# Sheet3.net
KiCad netlist of a schematic drawn in Altium Designer
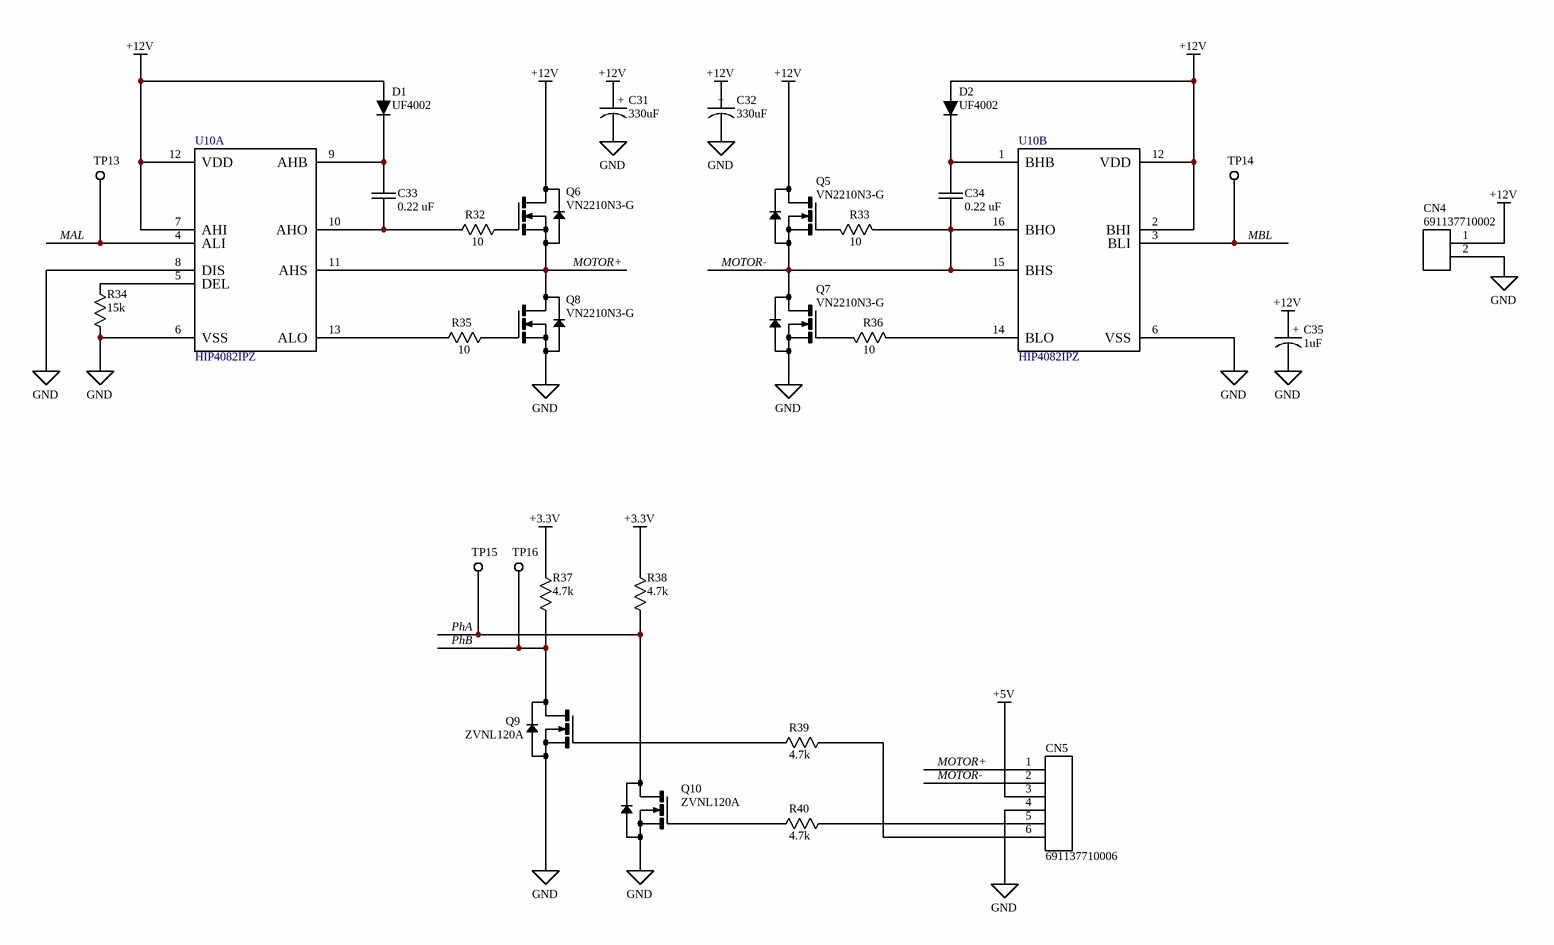
[diagram p0: Sheet3.SchDoc]

(export (version "E")
  (design (tool "Eeschema 10.0.6"))
  (components
    (comp (ref "C31")
      (value "330uF")
      (footprint "ECA-1EM331")
      (description "330 uF, 25 V Aluminum Electrolytic Capacitor")
      (fields
        (field (name "MANUFACTURER") "Panasonic Corporation of North America")
        (field (name "PARTNUMBER") "ECA-1EM331")
      )
      (libsource (lib "Schlib1") (part "ECA-1EM331"))
    )
    (comp (ref "C32")
      (value "330uF")
      (footprint "ECA-1EM331")
      (description "330 uF, 25 V Aluminum Electrolytic Capacitor")
      (fields
        (field (name "MANUFACTURER") "Panasonic Corporation of North America")
        (field (name "PARTNUMBER") "ECA-1EM331")
      )
      (libsource (lib "") (part "ECA-1EM331_1"))
    )
    (comp (ref "C33")
      (value "0.22 uF")
      (footprint "C330C224K1R5TA7301")
      (description "0.22 uF, 100 V Ceramic Capacitor")
      (fields (field (name "MANUFACTURER") "Kemet") (field (name "PARTNUMBER") "C330C224K1R5TA7301"))
      (libsource (lib "Schlib1") (part "C330C224K1R5TA7301"))
    )
    (comp (ref "C34")
      (value "0.22 uF")
      (footprint "C330C224K1R5TA7301")
      (description "0.22 uF, 100 V Ceramic Capacitor")
      (fields (field (name "MANUFACTURER") "Kemet") (field (name "PARTNUMBER") "C330C224K1R5TA7301"))
      (libsource (lib "Schlib1") (part "C330C224K1R5TA7301"))
    )
    (comp (ref "C35")
      (value "1uF")
      (footprint "SR215E105MAR")
      (description "1 uF, 50 V Ceramic Capacitor")
      (fields (field (name "MANUFACTURER") "AVX Corporation") (field (name "PARTNUMBER") "SR215E105MAR"))
      (libsource (lib "Schlib1") (part "SR215E105MAR"))
    )
    (comp (ref "CN4")
      (value "691137710002")
      (footprint "691137710002")
      (description "TERM BLK 2POS SIDE ENTRY 5MM PCB")
      (fields (field (name "MANUFACTURER") "Wurth Elektronk"))
      (libsource (lib "Schlib1") (part "691137710002"))
    )
    (comp (ref "CN5")
      (value "691137710006")
      (footprint "691137710006")
      (description "TERM BLK 6POS SIDE ENTRY 5MM PCB")
      (fields (field (name "MANUFACTURER") "Wurth Elektronik"))
      (libsource (lib "Schlib1") (part "691137710006"))
    )
    (comp (ref "D1")
      (value "UF4002")
      (footprint "UF4002")
      (description "Fast Rectifier")
      (fields (field (name "MANUFACTURER") "ON Semiconductor"))
      (libsource (lib "Schlib1") (part "UF4002"))
    )
    (comp (ref "D2")
      (value "UF4002")
      (footprint "UF4002")
      (description "Fast Rectifier")
      (fields (field (name "MANUFACTURER") "ON Semiconductor"))
      (libsource (lib "Schlib1") (part "UF4002"))
    )
    (comp (ref "Q5")
      (value "VN2210N3-G")
      (footprint "VN2210N3-G")
      (description "N-Channel Enhancement-Mode Vertical DMOS FETs")
      (fields (field (name "MANUFACTURER") "Supertex Inc."))
      (libsource (lib "") (part "VN2210N3-G_1"))
    )
    (comp (ref "Q6")
      (value "VN2210N3-G")
      (footprint "VN2210N3-G")
      (description "N-Channel Enhancement-Mode Vertical DMOS FETs")
      (fields (field (name "MANUFACTURER") "Supertex Inc."))
      (libsource (lib "Schlib1") (part "VN2210N3-G"))
    )
    (comp (ref "Q7")
      (value "VN2210N3-G")
      (footprint "VN2210N3-G")
      (description "N-Channel Enhancement-Mode Vertical DMOS FETs")
      (fields (field (name "MANUFACTURER") "Supertex Inc."))
      (libsource (lib "") (part "VN2210N3-G_1"))
    )
    (comp (ref "Q8")
      (value "VN2210N3-G")
      (footprint "VN2210N3-G")
      (description "N-Channel Enhancement-Mode Vertical DMOS FETs")
      (fields (field (name "MANUFACTURER") "Supertex Inc."))
      (libsource (lib "Schlib1") (part "VN2210N3-G"))
    )
    (comp (ref "Q9")
      (value "ZVNL120A")
      (footprint "ZVNL120A")
      (description "25V, 31 A, N-Channel Power MOSFET")
      (fields (field (name "MANUFACTURER") "Diodes Inc"))
      (libsource (lib "Schlib1") (part "ZVNL120A"))
    )
    (comp (ref "Q10")
      (value "ZVNL120A")
      (footprint "ZVNL120A")
      (description "25V, 31 A, N-Channel Power MOSFET")
      (fields (field (name "MANUFACTURER") "Diodes Inc"))
      (libsource (lib "Schlib1") (part "ZVNL120A"))
    )
    (comp (ref "R32")
      (value "10")
      (footprint "1/2WattResistor")
      (description "10 Ohmn, ±5%, 0.5W Thru-Hole Resistor")
      (fields (field (name "MANUFACTURER") "Generic") (field (name "PARTNUMBER") "RES10-500mW-THRU-HOLE"))
      (libsource (lib "Schlib1") (part "RES10-500mW-THRU-HOLE"))
    )
    (comp (ref "R33")
      (value "10")
      (footprint "1/2WattResistor")
      (description "10 Ohmn, ±5%, 0.5W Thru-Hole Resistor")
      (fields (field (name "MANUFACTURER") "Generic") (field (name "PARTNUMBER") "RES10-500mW-THRU-HOLE"))
      (libsource (lib "Schlib1") (part "RES10-500mW-THRU-HOLE"))
    )
    (comp (ref "R34")
      (value "15k")
      (footprint "1/2WattResistor")
      (description "15 kOhm, ±5%, 0.5W Thru-Hole Resistor")
      (fields (field (name "MANUFACTURER") "Generic") (field (name "PARTNUMBER") "RES15k-500mW-THRU-HOLE"))
      (libsource (lib "Schlib1") (part "RES15k-500mW-THRU-HOLE"))
    )
    (comp (ref "R35")
      (value "10")
      (footprint "1/2WattResistor")
      (description "10 Ohmn, ±5%, 0.5W Thru-Hole Resistor")
      (fields (field (name "MANUFACTURER") "Generic") (field (name "PARTNUMBER") "RES10-500mW-THRU-HOLE"))
      (libsource (lib "Schlib1") (part "RES10-500mW-THRU-HOLE"))
    )
    (comp (ref "R36")
      (value "10")
      (footprint "1/2WattResistor")
      (description "10 Ohmn, ±5%, 0.5W Thru-Hole Resistor")
      (fields (field (name "MANUFACTURER") "Generic") (field (name "PARTNUMBER") "RES10-500mW-THRU-HOLE"))
      (libsource (lib "Schlib1") (part "RES10-500mW-THRU-HOLE"))
    )
    (comp (ref "R37")
      (value "4.7k")
      (footprint "1/2WattResistor")
      (description "4.7 kOhm, ±5%, 0.5W Thru-Hole Resistor")
      (fields (field (name "MANUFACTURER") "Generic") (field (name "PARTNUMBER") "RES4k7-500mW-THRU-HOLE"))
      (libsource (lib "Schlib1") (part "RES4k7-500mW-THRU-HOLE"))
    )
    (comp (ref "R38")
      (value "4.7k")
      (footprint "1/2WattResistor")
      (description "4.7 kOhm, ±5%, 0.5W Thru-Hole Resistor")
      (fields (field (name "MANUFACTURER") "Generic") (field (name "PARTNUMBER") "RES4k7-500mW-THRU-HOLE"))
      (libsource (lib "Schlib1") (part "RES4k7-500mW-THRU-HOLE"))
    )
    (comp (ref "R39")
      (value "4.7k")
      (footprint "1/2WattResistor")
      (description "4.7 kOhm, ±5%, 0.5W Thru-Hole Resistor")
      (fields (field (name "MANUFACTURER") "Generic") (field (name "PARTNUMBER") "RES4k7-500mW-THRU-HOLE"))
      (libsource (lib "Schlib1") (part "RES4k7-500mW-THRU-HOLE"))
    )
    (comp (ref "R40")
      (value "4.7k")
      (footprint "1/2WattResistor")
      (description "4.7 kOhm, ±5%, 0.5W Thru-Hole Resistor")
      (fields (field (name "MANUFACTURER") "Generic") (field (name "PARTNUMBER") "RES4k7-500mW-THRU-HOLE"))
      (libsource (lib "Schlib1") (part "RES4k7-500mW-THRU-HOLE"))
    )
    (comp (ref "TP13")
      (value "TESTPOINT-2MM")
      (footprint "TESTPOINT-2MM")
      (description "Test Point 2MM diameter")
      (libsource (lib "Schlib1") (part "TESTPOINT-2MM"))
    )
    (comp (ref "TP14")
      (value "TESTPOINT-2MM")
      (footprint "TESTPOINT-2MM")
      (description "Test Point 2MM diameter")
      (libsource (lib "Schlib1") (part "TESTPOINT-2MM"))
    )
    (comp (ref "TP15")
      (value "TESTPOINT-2MM")
      (footprint "TESTPOINT-2MM")
      (description "Test Point 2MM diameter")
      (libsource (lib "Schlib1") (part "TESTPOINT-2MM"))
    )
    (comp (ref "TP16")
      (value "TESTPOINT-2MM")
      (footprint "TESTPOINT-2MM")
      (description "Test Point 2MM diameter")
      (libsource (lib "Schlib1") (part "TESTPOINT-2MM"))
    )
    (comp (ref "U10")
      (value "HIP4082IPZ")
      (footprint "HIP4082IPZ")
      (description "80V, 1.25A Peak Current H-Bridge FET Driver")
      (fields (field (name "MANUFACTURER") "Renesas"))
      (libsource (lib "Schlib1") (part "HIP4082IPZ"))
    )
  )
  (nets
    (net (code "1") (name "+3.3V") (class "Default")
      (node (ref "R37") (pin "2") (pinfunction "2_2") (pintype "passive"))
      (node (ref "R38") (pin "2") (pinfunction "2_2") (pintype "passive"))
    )
    (net (code "2") (name "+5V") (class "Default")
      (node (ref "CN5") (pin "3") (pinfunction "3_3") (pintype "passive"))
    )
    (net (code "3") (name "+12V") (class "Default")
      (node (ref "C31") (pin "1") (pinfunction "1_1") (pintype "passive"))
      (node (ref "C32") (pin "1") (pinfunction "1_1") (pintype "passive"))
      (node (ref "C35") (pin "1") (pinfunction "1_1") (pintype "passive"))
      (node (ref "CN4") (pin "1") (pinfunction "1_1") (pintype "passive"))
      (node (ref "D1") (pin "A") (pinfunction "A_A") (pintype "passive"))
      (node (ref "D2") (pin "A") (pinfunction "A_A") (pintype "passive"))
      (node (ref "Q5") (pin "3") (pinfunction "3_3") (pintype "passive"))
      (node (ref "Q6") (pin "3") (pinfunction "3_3") (pintype "passive"))
      (node (ref "U10") (pin "12") (pinfunction "VDD_12") (pintype "passive"))
      (node (ref "U10") (pin "2") (pinfunction "BHI_2") (pintype "passive"))
      (node (ref "U10") (pin "7") (pinfunction "AHI_7") (pintype "passive"))
    )
    (net (code "4") (name "/MAL") (class "Default")
      (node (ref "TP13") (pin "1") (pintype "passive"))
      (node (ref "U10") (pin "4") (pinfunction "ALI_4") (pintype "passive"))
    )
    (net (code "5") (name "/MBL") (class "Default")
      (node (ref "TP14") (pin "1") (pintype "passive"))
      (node (ref "U10") (pin "3") (pinfunction "BLI_3") (pintype "passive"))
    )
    (net (code "6") (name "/MOTOR+") (class "Default")
      (node (ref "CN5") (pin "1") (pinfunction "1_1") (pintype "passive"))
      (node (ref "Q6") (pin "1") (pinfunction "1_1") (pintype "passive"))
      (node (ref "Q8") (pin "3") (pinfunction "3_3") (pintype "passive"))
      (node (ref "U10") (pin "11") (pinfunction "AHS_11") (pintype "passive"))
    )
    (net (code "7") (name "/MOTOR-") (class "Default")
      (node (ref "C34") (pin "2") (pinfunction "2_2") (pintype "passive"))
      (node (ref "CN5") (pin "2") (pinfunction "2_2") (pintype "passive"))
      (node (ref "Q5") (pin "1") (pinfunction "1_1") (pintype "passive"))
      (node (ref "Q7") (pin "3") (pinfunction "3_3") (pintype "passive"))
      (node (ref "R33") (pin "1") (pinfunction "1_1") (pintype "passive"))
      (node (ref "U10") (pin "15") (pinfunction "BHS_15") (pintype "passive"))
      (node (ref "U10") (pin "16") (pinfunction "BHO_16") (pintype "passive"))
    )
    (net (code "8") (name "/PhA") (class "Default")
      (node (ref "Q10") (pin "3") (pinfunction "3_3") (pintype "passive"))
      (node (ref "R38") (pin "1") (pinfunction "1_1") (pintype "passive"))
      (node (ref "TP15") (pin "1") (pintype "passive"))
    )
    (net (code "9") (name "/PhB") (class "Default")
      (node (ref "Q9") (pin "3") (pinfunction "3_3") (pintype "passive"))
      (node (ref "R37") (pin "1") (pinfunction "1_1") (pintype "passive"))
      (node (ref "TP16") (pin "1") (pintype "passive"))
    )
    (net (code "10") (name "GND") (class "Default")
      (node (ref "C31") (pin "2") (pinfunction "2_2") (pintype "passive"))
      (node (ref "C32") (pin "2") (pinfunction "2_2") (pintype "passive"))
      (node (ref "C35") (pin "2") (pinfunction "2_2") (pintype "passive"))
      (node (ref "CN4") (pin "2") (pinfunction "2_2") (pintype "passive"))
      (node (ref "CN5") (pin "4") (pinfunction "4_4") (pintype "passive"))
      (node (ref "Q10") (pin "1") (pinfunction "1_1") (pintype "passive"))
      (node (ref "Q7") (pin "1") (pinfunction "1_1") (pintype "passive"))
      (node (ref "Q8") (pin "1") (pinfunction "1_1") (pintype "passive"))
      (node (ref "Q9") (pin "1") (pinfunction "1_1") (pintype "passive"))
      (node (ref "R34") (pin "1") (pinfunction "1_1") (pintype "passive"))
      (node (ref "U10") (pin "6") (pinfunction "VSS_6") (pintype "passive"))
      (node (ref "U10") (pin "8") (pinfunction "DIS_8") (pintype "passive"))
    )
    (net (code "11") (name "Net-(CN5-Pad5)") (class "Default")
      (node (ref "CN5") (pin "5") (pinfunction "5_5") (pintype "passive"))
      (node (ref "R40") (pin "2") (pinfunction "2_2") (pintype "passive"))
    )
    (net (code "12") (name "Net-(CN5-Pad6)") (class "Default")
      (node (ref "CN5") (pin "6") (pinfunction "6_6") (pintype "passive"))
      (node (ref "R39") (pin "2") (pinfunction "2_2") (pintype "passive"))
    )
    (net (code "13") (name "Net-(Q5-Pad2)") (class "Default")
      (node (ref "Q5") (pin "2") (pinfunction "2_2") (pintype "passive"))
      (node (ref "R33") (pin "2") (pinfunction "2_2") (pintype "passive"))
    )
    (net (code "14") (name "Net-(Q6-Pad2)") (class "Default")
      (node (ref "Q6") (pin "2") (pinfunction "2_2") (pintype "passive"))
      (node (ref "R32") (pin "2") (pinfunction "2_2") (pintype "passive"))
    )
    (net (code "15") (name "Net-(Q7-Pad2)") (class "Default")
      (node (ref "Q7") (pin "2") (pinfunction "2_2") (pintype "passive"))
      (node (ref "R36") (pin "2") (pinfunction "2_2") (pintype "passive"))
    )
    (net (code "16") (name "Net-(Q8-Pad2)") (class "Default")
      (node (ref "Q8") (pin "2") (pinfunction "2_2") (pintype "passive"))
      (node (ref "R35") (pin "2") (pinfunction "2_2") (pintype "passive"))
    )
    (net (code "17") (name "Net-(Q9-Pad2)") (class "Default")
      (node (ref "Q9") (pin "2") (pinfunction "2_2") (pintype "passive"))
      (node (ref "R39") (pin "1") (pinfunction "1_1") (pintype "passive"))
    )
    (net (code "18") (name "Net-(Q10-Pad2)") (class "Default")
      (node (ref "Q10") (pin "2") (pinfunction "2_2") (pintype "passive"))
      (node (ref "R40") (pin "1") (pinfunction "1_1") (pintype "passive"))
    )
    (net (code "19") (name "Net-(U10A-AHB)") (class "Default")
      (node (ref "C33") (pin "1") (pinfunction "1_1") (pintype "passive"))
      (node (ref "D1") (pin "K") (pinfunction "K_K") (pintype "passive"))
      (node (ref "U10") (pin "9") (pinfunction "AHB_9") (pintype "passive"))
    )
    (net (code "20") (name "Net-(U10A-AHO)") (class "Default")
      (node (ref "C33") (pin "2") (pinfunction "2_2") (pintype "passive"))
      (node (ref "R32") (pin "1") (pinfunction "1_1") (pintype "passive"))
      (node (ref "U10") (pin "10") (pinfunction "AHO_10") (pintype "passive"))
    )
    (net (code "21") (name "Net-(U10A-ALO)") (class "Default")
      (node (ref "R35") (pin "1") (pinfunction "1_1") (pintype "passive"))
      (node (ref "U10") (pin "13") (pinfunction "ALO_13") (pintype "passive"))
    )
    (net (code "22") (name "Net-(U10A-DEL)") (class "Default")
      (node (ref "R34") (pin "2") (pinfunction "2_2") (pintype "passive"))
      (node (ref "U10") (pin "5") (pinfunction "DEL_5") (pintype "passive"))
    )
    (net (code "23") (name "Net-(U10B-BHB)") (class "Default")
      (node (ref "C34") (pin "1") (pinfunction "1_1") (pintype "passive"))
      (node (ref "D2") (pin "K") (pinfunction "K_K") (pintype "passive"))
      (node (ref "U10") (pin "1") (pinfunction "BHB_1") (pintype "passive"))
    )
    (net (code "24") (name "Net-(U10B-BLO)") (class "Default")
      (node (ref "R36") (pin "1") (pinfunction "1_1") (pintype "passive"))
      (node (ref "U10") (pin "14") (pinfunction "BLO_14") (pintype "passive"))
    )
  )
)
